# 608_donkey_030200.net
KiCad netlist of a schematic drawn in EAGLE
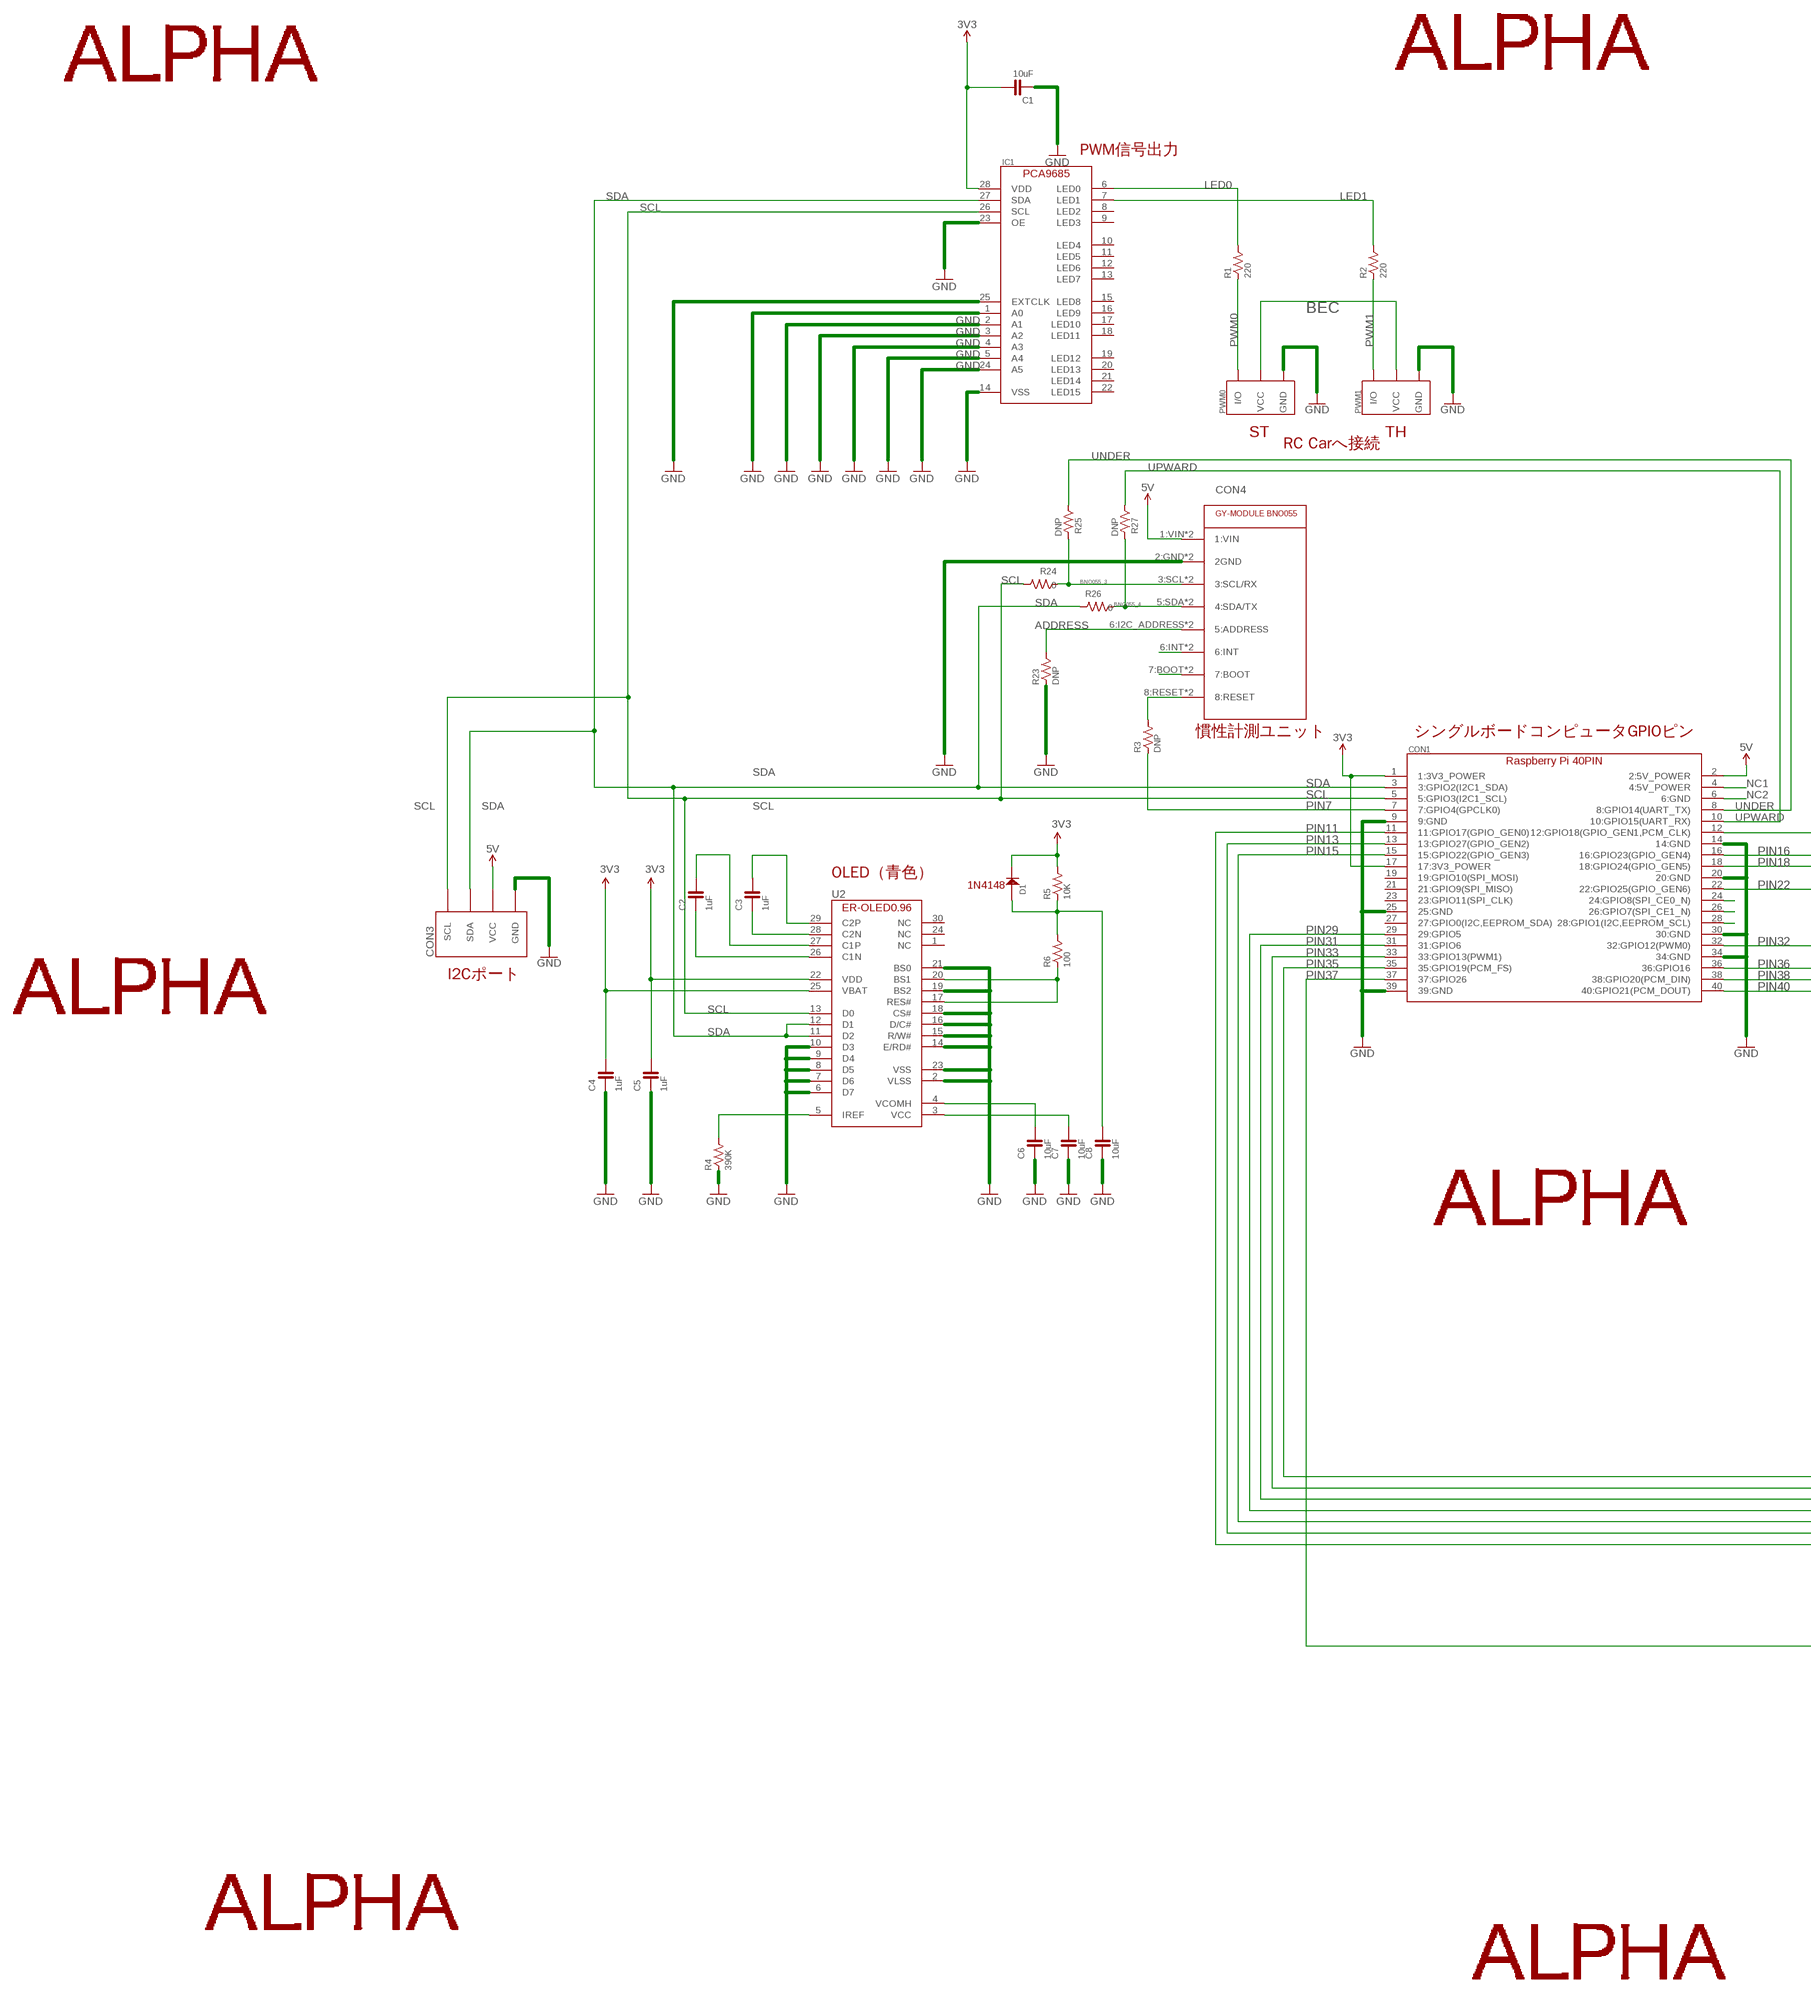
[diagram p0: schematic, sheet 1, part 1 of 3]
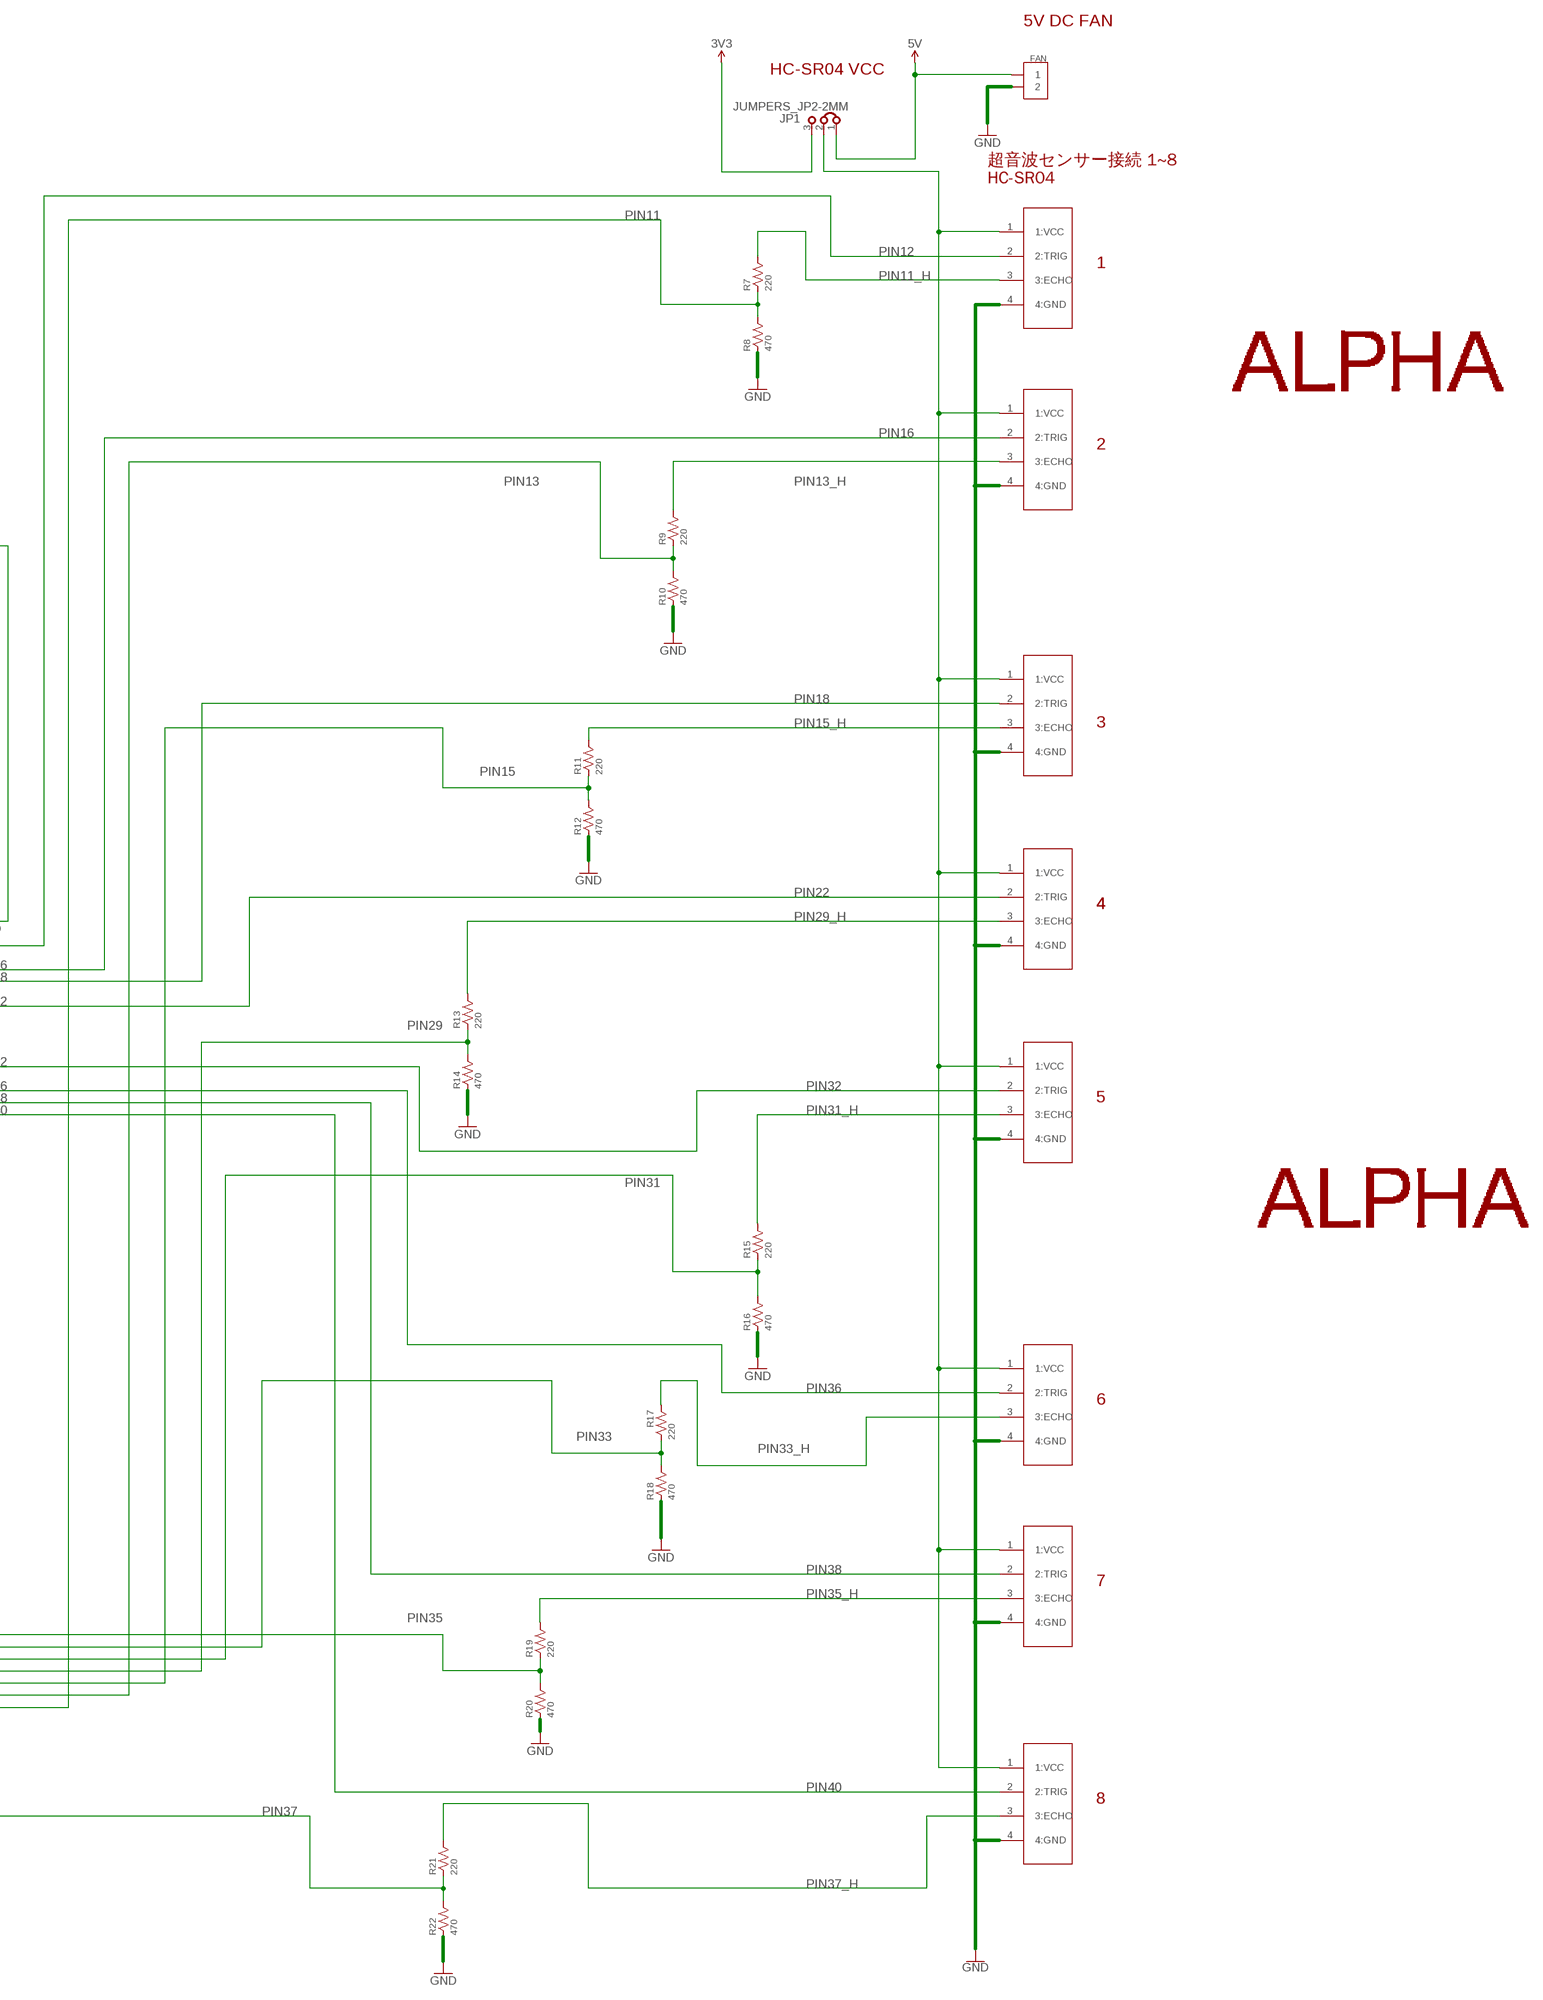
[diagram p1: schematic, sheet 1, part 2 of 3]
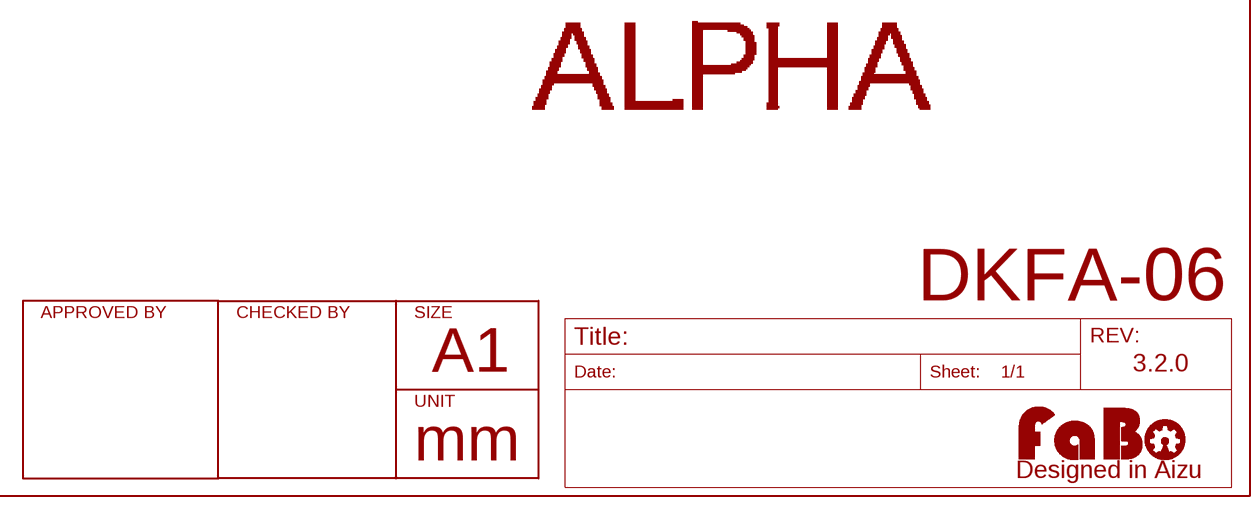
[diagram p2: schematic, sheet 1, part 3 of 3]

(export (version "E")
  (design (tool "Eeschema 10.0.6"))
  (components
    (comp (ref "C1")
      (value "10uF")
      (footprint "eagle-import:0603")
      (libsource (lib "eagle-import") (part "CAPACITOR-0603"))
    )
    (comp (ref "C2")
      (value "1uF")
      (footprint "eagle-import:0603-BOTTOM")
      (libsource (lib "eagle-import") (part "CAPACITOR-0603-BOTTOM"))
    )
    (comp (ref "C3")
      (value "1uF")
      (footprint "eagle-import:0603-BOTTOM")
      (libsource (lib "eagle-import") (part "CAPACITOR-0603-BOTTOM"))
    )
    (comp (ref "C4")
      (value "1uF")
      (footprint "eagle-import:0603-BOTTOM")
      (libsource (lib "eagle-import") (part "CAPACITOR-0603-BOTTOM"))
    )
    (comp (ref "C5")
      (value "1uF")
      (footprint "eagle-import:0603-BOTTOM")
      (libsource (lib "eagle-import") (part "CAPACITOR-0603-BOTTOM"))
    )
    (comp (ref "C6")
      (value "10uF")
      (footprint "eagle-import:0603-BOTTOM")
      (libsource (lib "eagle-import") (part "CAPACITOR-0603-BOTTOM"))
    )
    (comp (ref "C7")
      (value "10uF")
      (footprint "eagle-import:0603-BOTTOM")
      (libsource (lib "eagle-import") (part "CAPACITOR-0603-BOTTOM"))
    )
    (comp (ref "C8")
      (value "10uF")
      (footprint "eagle-import:0603-BOTTOM")
      (libsource (lib "eagle-import") (part "CAPACITOR-0603-BOTTOM"))
    )
    (comp (ref "CON1")
      (value "RASPBERRYPI_SHEILD")
      (footprint "eagle-import:RASPBERRY_PI_SHILED")
      (libsource (lib "eagle-import") (part "RASPBERRYPI_SHEILD"))
    )
    (comp (ref "CON3")
      (value "FABO_BRICK_I2C-S04B-PASK-2")
      (footprint "eagle-import:FABO_BRICK_I2C_S04B-PASK-2")
      (libsource (lib "eagle-import") (part "FABO_BRICK_I2C-S04B-PASK-2"))
    )
    (comp (ref "CON4")
      (value "GY-MODULE_BNO055")
      (footprint "eagle-import:GY-MODULE_BNO055")
      (libsource (lib "eagle-import") (part "GY-MODULE_BNO055"))
    )
    (comp (ref "D1")
      (value "1N4148")
      (footprint "eagle-import:1N4148W")
      (libsource (lib "eagle-import") (part "1N4148"))
    )
    (comp (ref "FAN")
      (value "PIN_1X2")
      (footprint "eagle-import:PIN_1X2")
      (libsource (lib "eagle-import") (part "PIN_1X2"))
    )
    (comp (ref "HC1")
      (value "HC-SR04CONHS-SR04CON-SPEACING")
      (footprint "eagle-import:HC-SR04CON-SPEACE")
      (libsource (lib "eagle-import") (part "HC-SR04CONHS-SR04CON-SPEACING"))
    )
    (comp (ref "HC2")
      (value "HC-SR04CONHS-SR04CON-SPEACING")
      (footprint "eagle-import:HC-SR04CON-SPEACE")
      (libsource (lib "eagle-import") (part "HC-SR04CONHS-SR04CON-SPEACING"))
    )
    (comp (ref "HC3")
      (value "HC-SR04CONHS-SR04CON-SPEACING")
      (footprint "eagle-import:HC-SR04CON-SPEACE")
      (libsource (lib "eagle-import") (part "HC-SR04CONHS-SR04CON-SPEACING"))
    )
    (comp (ref "HC4")
      (value "HC-SR04CONHS-SR04CON-SPEACING")
      (footprint "eagle-import:HC-SR04CON-SPEACE")
      (libsource (lib "eagle-import") (part "HC-SR04CONHS-SR04CON-SPEACING"))
    )
    (comp (ref "HC5")
      (value "HC-SR04CONHS-SR04CON-SPEACING")
      (footprint "eagle-import:HC-SR04CON-SPEACE")
      (libsource (lib "eagle-import") (part "HC-SR04CONHS-SR04CON-SPEACING"))
    )
    (comp (ref "HC6")
      (value "HC-SR04CONHS-SR04CON-SPEACING")
      (footprint "eagle-import:HC-SR04CON-SPEACE")
      (libsource (lib "eagle-import") (part "HC-SR04CONHS-SR04CON-SPEACING"))
    )
    (comp (ref "HC7")
      (value "HC-SR04CONHS-SR04CON-SPEACING")
      (footprint "eagle-import:HC-SR04CON-SPEACE")
      (libsource (lib "eagle-import") (part "HC-SR04CONHS-SR04CON-SPEACING"))
    )
    (comp (ref "HC8")
      (value "HC-SR04CONHS-SR04CON-SPEACING")
      (footprint "eagle-import:HC-SR04CON-SPEACE")
      (libsource (lib "eagle-import") (part "HC-SR04CONHS-SR04CON-SPEACING"))
    )
    (comp (ref "IC1")
      (value "PCA9685BS")
      (footprint "eagle-import:PCA9685")
      (libsource (lib "eagle-import") (part "PCA9685BS"))
    )
    (comp (ref "JP1")
      (value "JUMPERS_JP2-2MM")
      (footprint "eagle-import:JUMPERS_JP2-2MM")
      (libsource (lib "eagle-import") (part "JUMPERS_JP2-2MM"))
    )
    (comp (ref "LOGO1")
      (value "LOGO_FABO-M")
      (footprint "eagle-import:LOGO_FABO_M")
      (libsource (lib "eagle-import") (part "LOGO_FABO-M"))
    )
    (comp (ref "PWM0")
      (value "PWM0")
      (footprint "eagle-import:PIN_1X3_NARROW")
      (libsource (lib "eagle-import") (part "FABO-BRICK-3PIN_HEADER"))
    )
    (comp (ref "PWM1")
      (value "PWM1")
      (footprint "eagle-import:PIN_1X3_NARROW")
      (libsource (lib "eagle-import") (part "FABO-BRICK-3PIN_HEADER"))
    )
    (comp (ref "R1")
      (value "220")
      (footprint "eagle-import:0603")
      (libsource (lib "eagle-import") (part "RESISTOR-0603"))
    )
    (comp (ref "R2")
      (value "220")
      (footprint "eagle-import:0603")
      (libsource (lib "eagle-import") (part "RESISTOR-0603"))
    )
    (comp (ref "R3")
      (value "DNP")
      (footprint "eagle-import:0603-BOTTOM")
      (libsource (lib "eagle-import") (part "RESISTOR-0603-BOTTOM"))
    )
    (comp (ref "R4")
      (value "390K")
      (footprint "eagle-import:0603-BOTTOM")
      (libsource (lib "eagle-import") (part "RESISTOR-0603-BOTTOM"))
    )
    (comp (ref "R5")
      (value "10K")
      (footprint "eagle-import:0603-BOTTOM")
      (libsource (lib "eagle-import") (part "RESISTOR-0603-BOTTOM"))
    )
    (comp (ref "R6")
      (value "100")
      (footprint "eagle-import:0603-BOTTOM")
      (libsource (lib "eagle-import") (part "RESISTOR-0603-BOTTOM"))
    )
    (comp (ref "R7")
      (value "220")
      (footprint "eagle-import:0603")
      (libsource (lib "eagle-import") (part "RESISTOR-0603"))
    )
    (comp (ref "R8")
      (value "470")
      (footprint "eagle-import:0603")
      (libsource (lib "eagle-import") (part "RESISTOR-0603"))
    )
    (comp (ref "R9")
      (value "220")
      (footprint "eagle-import:0603")
      (libsource (lib "eagle-import") (part "RESISTOR-0603"))
    )
    (comp (ref "R10")
      (value "470")
      (footprint "eagle-import:0603")
      (libsource (lib "eagle-import") (part "RESISTOR-0603"))
    )
    (comp (ref "R11")
      (value "220")
      (footprint "eagle-import:0603")
      (libsource (lib "eagle-import") (part "RESISTOR-0603"))
    )
    (comp (ref "R12")
      (value "470")
      (footprint "eagle-import:0603")
      (libsource (lib "eagle-import") (part "RESISTOR-0603"))
    )
    (comp (ref "R13")
      (value "220")
      (footprint "eagle-import:0603")
      (libsource (lib "eagle-import") (part "RESISTOR-0603"))
    )
    (comp (ref "R14")
      (value "470")
      (footprint "eagle-import:0603")
      (libsource (lib "eagle-import") (part "RESISTOR-0603"))
    )
    (comp (ref "R15")
      (value "220")
      (footprint "eagle-import:0603")
      (libsource (lib "eagle-import") (part "RESISTOR-0603"))
    )
    (comp (ref "R16")
      (value "470")
      (footprint "eagle-import:0603")
      (libsource (lib "eagle-import") (part "RESISTOR-0603"))
    )
    (comp (ref "R17")
      (value "220")
      (footprint "eagle-import:0603")
      (libsource (lib "eagle-import") (part "RESISTOR-0603"))
    )
    (comp (ref "R18")
      (value "470")
      (footprint "eagle-import:0603")
      (libsource (lib "eagle-import") (part "RESISTOR-0603"))
    )
    (comp (ref "R19")
      (value "220")
      (footprint "eagle-import:0603")
      (libsource (lib "eagle-import") (part "RESISTOR-0603"))
    )
    (comp (ref "R20")
      (value "470")
      (footprint "eagle-import:0603")
      (libsource (lib "eagle-import") (part "RESISTOR-0603"))
    )
    (comp (ref "R21")
      (value "220")
      (footprint "eagle-import:0603")
      (libsource (lib "eagle-import") (part "RESISTOR-0603"))
    )
    (comp (ref "R22")
      (value "470")
      (footprint "eagle-import:0603")
      (libsource (lib "eagle-import") (part "RESISTOR-0603"))
    )
    (comp (ref "R23")
      (value "DNP")
      (footprint "eagle-import:0603-BOTTOM")
      (libsource (lib "eagle-import") (part "RESISTOR-0603-BOTTOM"))
    )
    (comp (ref "R24")
      (value "0")
      (footprint "eagle-import:0603-BOTTOM")
      (libsource (lib "eagle-import") (part "RESISTOR-0603-BOTTOM"))
    )
    (comp (ref "R25")
      (value "DNP")
      (footprint "eagle-import:0603-BOTTOM")
      (libsource (lib "eagle-import") (part "RESISTOR-0603-BOTTOM"))
    )
    (comp (ref "R26")
      (value "0")
      (footprint "eagle-import:0603-BOTTOM")
      (libsource (lib "eagle-import") (part "RESISTOR-0603-BOTTOM"))
    )
    (comp (ref "R27")
      (value "DNP")
      (footprint "eagle-import:0603-BOTTOM")
      (libsource (lib "eagle-import") (part "RESISTOR-0603-BOTTOM"))
    )
    (comp (ref "U2")
      (value "ER-OLED0.96-1ER-CON30HT-1_REV2")
      (footprint "eagle-import:ER-CON30HT-1_REV2")
      (libsource (lib "eagle-import") (part "ER-OLED0.96-1ER-CON30HT-1_REV2"))
    )
  )
  (nets
    (net (code "1") (name "/ADDRESS") (class "Default")
      (node (ref "CON4") (pin "13:ADDRESSS") (pinfunction "5:ADDRESS_13:ADDRESSS") (pintype "bidirectional"))
      (node (ref "CON4") (pin "6:I2C_ADDRESS") (pinfunction "5:ADDRESS_6:I2C_ADDRESS") (pintype "bidirectional"))
      (node (ref "R23") (pin "2") (pinfunction "2_2") (pintype "bidirectional"))
    )
    (net (code "2") (name "/BEC") (class "Default")
      (node (ref "PWM0") (pin "2") (pinfunction "VCC_2") (pintype "bidirectional"))
      (node (ref "PWM1") (pin "2") (pinfunction "VCC_2") (pintype "bidirectional"))
    )
    (net (code "3") (name "/BNO055_3") (class "Default")
      (node (ref "CON4") (pin "11:SCL") (pinfunction "3:SCL/RX_11:SCL") (pintype "bidirectional"))
      (node (ref "CON4") (pin "3:SCL") (pinfunction "3:SCL/RX_3:SCL") (pintype "bidirectional"))
      (node (ref "R24") (pin "1") (pinfunction "1_1") (pintype "bidirectional"))
      (node (ref "R25") (pin "2") (pinfunction "2_2") (pintype "bidirectional"))
    )
    (net (code "4") (name "/BNO055_4") (class "Default")
      (node (ref "CON4") (pin "12:SDA") (pinfunction "4:SDA/TX_12:SDA") (pintype "bidirectional"))
      (node (ref "CON4") (pin "5:SDA") (pinfunction "4:SDA/TX_5:SDA") (pintype "bidirectional"))
      (node (ref "R26") (pin "1") (pinfunction "1_1") (pintype "bidirectional"))
      (node (ref "R27") (pin "2") (pinfunction "2_2") (pintype "bidirectional"))
    )
    (net (code "5") (name "/LED0") (class "Default")
      (node (ref "IC1") (pin "6") (pinfunction "LED0_6") (pintype "bidirectional"))
      (node (ref "R1") (pin "2") (pinfunction "2_2") (pintype "bidirectional"))
    )
    (net (code "6") (name "/LED1") (class "Default")
      (node (ref "IC1") (pin "7") (pinfunction "LED1_7") (pintype "bidirectional"))
      (node (ref "R2") (pin "2") (pinfunction "2_2") (pintype "bidirectional"))
    )
    (net (code "7") (name "/NC1") (class "Default")
      (node (ref "CON1") (pin "4") (pinfunction "4:5V_POWER_4") (pintype "power_in"))
    )
    (net (code "8") (name "/NC2") (class "Default")
      (node (ref "CON1") (pin "6") (pinfunction "6:GND_6") (pintype "power_in"))
    )
    (net (code "9") (name "/PIN7") (class "Default")
      (node (ref "CON1") (pin "7") (pinfunction "7:GPIO4(GPCLK0)_7") (pintype "bidirectional"))
      (node (ref "R3") (pin "1") (pinfunction "1_1") (pintype "bidirectional"))
    )
    (net (code "10") (name "/PIN11") (class "Default")
      (node (ref "CON1") (pin "11") (pinfunction "11:GPIO17(GPIO_GEN0)_11") (pintype "bidirectional"))
      (node (ref "R7") (pin "1") (pinfunction "1_1") (pintype "bidirectional"))
      (node (ref "R8") (pin "2") (pinfunction "2_2") (pintype "bidirectional"))
    )
    (net (code "11") (name "/PIN11_H") (class "Default")
      (node (ref "HC1") (pin "3") (pinfunction "3:ECHO_3") (pintype "bidirectional"))
      (node (ref "R7") (pin "2") (pinfunction "2_2") (pintype "bidirectional"))
    )
    (net (code "12") (name "/PIN12") (class "Default")
      (node (ref "CON1") (pin "12") (pinfunction "12:GPIO18(GPIO_GEN1,PCM_CLK)_12") (pintype "bidirectional"))
      (node (ref "HC1") (pin "2") (pinfunction "2:TRIG_2") (pintype "bidirectional"))
    )
    (net (code "13") (name "/PIN13") (class "Default")
      (node (ref "CON1") (pin "13") (pinfunction "13:GPIO27(GPIO_GEN2)_13") (pintype "bidirectional"))
      (node (ref "R10") (pin "2") (pinfunction "2_2") (pintype "bidirectional"))
      (node (ref "R9") (pin "1") (pinfunction "1_1") (pintype "bidirectional"))
    )
    (net (code "14") (name "/PIN13_H") (class "Default")
      (node (ref "HC2") (pin "3") (pinfunction "3:ECHO_3") (pintype "bidirectional"))
      (node (ref "R9") (pin "2") (pinfunction "2_2") (pintype "bidirectional"))
    )
    (net (code "15") (name "/PIN15") (class "Default")
      (node (ref "CON1") (pin "15") (pinfunction "15:GPIO22(GPIO_GEN3)_15") (pintype "bidirectional"))
      (node (ref "R11") (pin "1") (pinfunction "1_1") (pintype "bidirectional"))
      (node (ref "R12") (pin "2") (pinfunction "2_2") (pintype "bidirectional"))
    )
    (net (code "16") (name "/PIN15_H") (class "Default")
      (node (ref "HC3") (pin "3") (pinfunction "3:ECHO_3") (pintype "bidirectional"))
      (node (ref "R11") (pin "2") (pinfunction "2_2") (pintype "bidirectional"))
    )
    (net (code "17") (name "/PIN16") (class "Default")
      (node (ref "CON1") (pin "16") (pinfunction "16:GPIO23(GPIO_GEN4)_16") (pintype "bidirectional"))
      (node (ref "HC2") (pin "2") (pinfunction "2:TRIG_2") (pintype "bidirectional"))
    )
    (net (code "18") (name "/PIN18") (class "Default")
      (node (ref "CON1") (pin "18") (pinfunction "18:GPIO24(GPIO_GEN5)_18") (pintype "bidirectional"))
      (node (ref "HC3") (pin "2") (pinfunction "2:TRIG_2") (pintype "bidirectional"))
    )
    (net (code "19") (name "/PIN22") (class "Default")
      (node (ref "CON1") (pin "22") (pinfunction "22:GPIO25(GPIO_GEN6)_22") (pintype "bidirectional"))
      (node (ref "HC4") (pin "2") (pinfunction "2:TRIG_2") (pintype "bidirectional"))
    )
    (net (code "20") (name "/PIN29") (class "Default")
      (node (ref "CON1") (pin "29") (pinfunction "29:GPIO5_29") (pintype "bidirectional"))
      (node (ref "R13") (pin "1") (pinfunction "1_1") (pintype "bidirectional"))
      (node (ref "R14") (pin "2") (pinfunction "2_2") (pintype "bidirectional"))
    )
    (net (code "21") (name "/PIN29_H") (class "Default")
      (node (ref "HC4") (pin "3") (pinfunction "3:ECHO_3") (pintype "bidirectional"))
      (node (ref "R13") (pin "2") (pinfunction "2_2") (pintype "bidirectional"))
    )
    (net (code "22") (name "/PIN31") (class "Default")
      (node (ref "CON1") (pin "31") (pinfunction "31:GPIO6_31") (pintype "bidirectional"))
      (node (ref "R15") (pin "1") (pinfunction "1_1") (pintype "bidirectional"))
      (node (ref "R16") (pin "2") (pinfunction "2_2") (pintype "bidirectional"))
    )
    (net (code "23") (name "/PIN31_H") (class "Default")
      (node (ref "HC5") (pin "3") (pinfunction "3:ECHO_3") (pintype "bidirectional"))
      (node (ref "R15") (pin "2") (pinfunction "2_2") (pintype "bidirectional"))
    )
    (net (code "24") (name "/PIN32") (class "Default")
      (node (ref "CON1") (pin "32") (pinfunction "32:GPIO12(PWM0)_32") (pintype "bidirectional"))
      (node (ref "HC5") (pin "2") (pinfunction "2:TRIG_2") (pintype "bidirectional"))
    )
    (net (code "25") (name "/PIN33") (class "Default")
      (node (ref "CON1") (pin "33") (pinfunction "33:GPIO13(PWM1)_33") (pintype "bidirectional"))
      (node (ref "R17") (pin "1") (pinfunction "1_1") (pintype "bidirectional"))
      (node (ref "R18") (pin "2") (pinfunction "2_2") (pintype "bidirectional"))
    )
    (net (code "26") (name "/PIN33_H") (class "Default")
      (node (ref "HC6") (pin "3") (pinfunction "3:ECHO_3") (pintype "bidirectional"))
      (node (ref "R17") (pin "2") (pinfunction "2_2") (pintype "bidirectional"))
    )
    (net (code "27") (name "/PIN35") (class "Default")
      (node (ref "CON1") (pin "35") (pinfunction "35:GPIO19(PCM_FS)_35") (pintype "bidirectional"))
      (node (ref "R19") (pin "1") (pinfunction "1_1") (pintype "bidirectional"))
      (node (ref "R20") (pin "2") (pinfunction "2_2") (pintype "bidirectional"))
    )
    (net (code "28") (name "/PIN35_H") (class "Default")
      (node (ref "HC7") (pin "3") (pinfunction "3:ECHO_3") (pintype "bidirectional"))
      (node (ref "R19") (pin "2") (pinfunction "2_2") (pintype "bidirectional"))
    )
    (net (code "29") (name "/PIN36") (class "Default")
      (node (ref "CON1") (pin "36") (pinfunction "36:GPIO16_36") (pintype "bidirectional"))
      (node (ref "HC6") (pin "2") (pinfunction "2:TRIG_2") (pintype "bidirectional"))
    )
    (net (code "30") (name "/PIN37") (class "Default")
      (node (ref "CON1") (pin "37") (pinfunction "37:GPIO26_37") (pintype "bidirectional"))
      (node (ref "R21") (pin "1") (pinfunction "1_1") (pintype "bidirectional"))
      (node (ref "R22") (pin "2") (pinfunction "2_2") (pintype "bidirectional"))
    )
    (net (code "31") (name "/PIN37_H") (class "Default")
      (node (ref "HC8") (pin "3") (pinfunction "3:ECHO_3") (pintype "bidirectional"))
      (node (ref "R21") (pin "2") (pinfunction "2_2") (pintype "bidirectional"))
    )
    (net (code "32") (name "/PIN38") (class "Default")
      (node (ref "CON1") (pin "38") (pinfunction "38:GPIO20(PCM_DIN)_38") (pintype "bidirectional"))
      (node (ref "HC7") (pin "2") (pinfunction "2:TRIG_2") (pintype "bidirectional"))
    )
    (net (code "33") (name "/PIN40") (class "Default")
      (node (ref "CON1") (pin "40") (pinfunction "40:GPIO21(PCM_DOUT)_40") (pintype "bidirectional"))
      (node (ref "HC8") (pin "2") (pinfunction "2:TRIG_2") (pintype "bidirectional"))
    )
    (net (code "34") (name "/PWM0") (class "Default")
      (node (ref "PWM0") (pin "1") (pinfunction "I/O_1") (pintype "bidirectional"))
      (node (ref "R1") (pin "1") (pinfunction "1_1") (pintype "bidirectional"))
    )
    (net (code "35") (name "/PWM1") (class "Default")
      (node (ref "PWM1") (pin "1") (pinfunction "I/O_1") (pintype "bidirectional"))
      (node (ref "R2") (pin "1") (pinfunction "1_1") (pintype "bidirectional"))
    )
    (net (code "36") (name "/SCL") (class "Default")
      (node (ref "CON1") (pin "5") (pinfunction "5:GPIO3(I2C1_SCL)_5") (pintype "bidirectional"))
      (node (ref "CON3") (pin "SCL") (pinfunction "SCL_SCL") (pintype "bidirectional"))
      (node (ref "IC1") (pin "26") (pinfunction "SCL_26") (pintype "bidirectional"))
      (node (ref "R24") (pin "2") (pinfunction "2_2") (pintype "bidirectional"))
      (node (ref "U2") (pin "13") (pinfunction "D0_13") (pintype "bidirectional"))
    )
    (net (code "37") (name "/SDA") (class "Default")
      (node (ref "CON1") (pin "3") (pinfunction "3:GPIO2(I2C1_SDA)_3") (pintype "bidirectional"))
      (node (ref "CON3") (pin "SDA") (pinfunction "SDA_SDA") (pintype "bidirectional"))
      (node (ref "IC1") (pin "27") (pinfunction "SDA_27") (pintype "bidirectional"))
      (node (ref "R26") (pin "2") (pinfunction "2_2") (pintype "bidirectional"))
      (node (ref "U2") (pin "11") (pinfunction "D2_11") (pintype "bidirectional"))
      (node (ref "U2") (pin "12") (pinfunction "D1_12") (pintype "bidirectional"))
    )
    (net (code "38") (name "/UNDER") (class "Default")
      (node (ref "CON1") (pin "8") (pinfunction "8:GPIO14(UART_TX)_8") (pintype "bidirectional"))
      (node (ref "R25") (pin "1") (pinfunction "1_1") (pintype "bidirectional"))
    )
    (net (code "39") (name "/UPWARD") (class "Default")
      (node (ref "CON1") (pin "10") (pinfunction "10:GPIO15(UART_RX)_10") (pintype "bidirectional"))
      (node (ref "R27") (pin "1") (pinfunction "1_1") (pintype "bidirectional"))
    )
    (net (code "40") (name "3V3") (class "Default")
      (node (ref "C1") (pin "2") (pinfunction "2_2") (pintype "passive"))
      (node (ref "C4") (pin "2") (pinfunction "2_2") (pintype "passive"))
      (node (ref "C5") (pin "2") (pinfunction "2_2") (pintype "passive"))
      (node (ref "CON1") (pin "1") (pinfunction "1:3V3_POWER_1") (pintype "power_in"))
      (node (ref "CON1") (pin "17") (pinfunction "17:3V3_POWER_17") (pintype "power_in"))
      (node (ref "D1") (pin "CATHODE") (pinfunction "CATHODE_CATHODE") (pintype "bidirectional"))
      (node (ref "IC1") (pin "28") (pinfunction "VDD_28") (pintype "bidirectional"))
      (node (ref "JP1") (pin "3") (pinfunction "3_3") (pintype "passive"))
      (node (ref "R5") (pin "2") (pinfunction "2_2") (pintype "bidirectional"))
      (node (ref "U2") (pin "22") (pinfunction "VDD_22") (pintype "bidirectional"))
      (node (ref "U2") (pin "25") (pinfunction "VBAT_25") (pintype "bidirectional"))
    )
    (net (code "41") (name "5V") (class "Default")
      (node (ref "CON1") (pin "2") (pinfunction "2:5V_POWER_2") (pintype "power_in"))
      (node (ref "CON3") (pin "VCC") (pinfunction "VCC_VCC") (pintype "bidirectional"))
      (node (ref "CON4") (pin "1:VIN") (pinfunction "1:VIN_1:VIN") (pintype "bidirectional"))
      (node (ref "CON4") (pin "9:VIN") (pinfunction "1:VIN_9:VIN") (pintype "bidirectional"))
      (node (ref "FAN") (pin "1") (pinfunction "1_1") (pintype "bidirectional"))
      (node (ref "JP1") (pin "1") (pinfunction "1_1") (pintype "passive"))
    )
    (net (code "42") (name "GND") (class "Default")
      (node (ref "C1") (pin "1") (pinfunction "1_1") (pintype "passive"))
      (node (ref "C4") (pin "1") (pinfunction "1_1") (pintype "passive"))
      (node (ref "C5") (pin "1") (pinfunction "1_1") (pintype "passive"))
      (node (ref "C6") (pin "1") (pinfunction "1_1") (pintype "passive"))
      (node (ref "C7") (pin "1") (pinfunction "1_1") (pintype "passive"))
      (node (ref "C8") (pin "1") (pinfunction "1_1") (pintype "passive"))
      (node (ref "CON1") (pin "14") (pinfunction "14:GND_14") (pintype "power_in"))
      (node (ref "CON1") (pin "20") (pinfunction "20:GND_20") (pintype "power_in"))
      (node (ref "CON1") (pin "25") (pinfunction "25:GND_25") (pintype "power_in"))
      (node (ref "CON1") (pin "30") (pinfunction "30:GND_30") (pintype "power_in"))
      (node (ref "CON1") (pin "34") (pinfunction "34:GND_34") (pintype "power_in"))
      (node (ref "CON1") (pin "39") (pinfunction "39:GND_39") (pintype "power_in"))
      (node (ref "CON1") (pin "9") (pinfunction "9:GND_9") (pintype "power_in"))
      (node (ref "CON3") (pin "GND") (pinfunction "GND_GND") (pintype "bidirectional"))
      (node (ref "CON4") (pin "10:GND") (pinfunction "2GND_10:GND") (pintype "bidirectional"))
      (node (ref "CON4") (pin "2:GND") (pinfunction "2GND_2:GND") (pintype "bidirectional"))
      (node (ref "FAN") (pin "2") (pinfunction "2_2") (pintype "bidirectional"))
      (node (ref "HC1") (pin "4") (pinfunction "4:GND_4") (pintype "bidirectional"))
      (node (ref "HC2") (pin "4") (pinfunction "4:GND_4") (pintype "bidirectional"))
      (node (ref "HC3") (pin "4") (pinfunction "4:GND_4") (pintype "bidirectional"))
      (node (ref "HC4") (pin "4") (pinfunction "4:GND_4") (pintype "bidirectional"))
      (node (ref "HC5") (pin "4") (pinfunction "4:GND_4") (pintype "bidirectional"))
      (node (ref "HC6") (pin "4") (pinfunction "4:GND_4") (pintype "bidirectional"))
      (node (ref "HC7") (pin "4") (pinfunction "4:GND_4") (pintype "bidirectional"))
      (node (ref "HC8") (pin "4") (pinfunction "4:GND_4") (pintype "bidirectional"))
      (node (ref "IC1") (pin "1") (pinfunction "A0_1") (pintype "bidirectional"))
      (node (ref "IC1") (pin "14") (pinfunction "VSS_14") (pintype "bidirectional"))
      (node (ref "IC1") (pin "2") (pinfunction "A1_2") (pintype "bidirectional"))
      (node (ref "IC1") (pin "23") (pinfunction "OE_23") (pintype "bidirectional"))
      (node (ref "IC1") (pin "24") (pinfunction "A5_24") (pintype "bidirectional"))
      (node (ref "IC1") (pin "25") (pinfunction "EXTCLK_25") (pintype "bidirectional"))
      (node (ref "IC1") (pin "3") (pinfunction "A2_3") (pintype "bidirectional"))
      (node (ref "IC1") (pin "4") (pinfunction "A3_4") (pintype "bidirectional"))
      (node (ref "IC1") (pin "5") (pinfunction "A4_5") (pintype "bidirectional"))
      (node (ref "PWM0") (pin "3") (pinfunction "GND_3") (pintype "bidirectional"))
      (node (ref "PWM1") (pin "3") (pinfunction "GND_3") (pintype "bidirectional"))
      (node (ref "R10") (pin "1") (pinfunction "1_1") (pintype "bidirectional"))
      (node (ref "R12") (pin "1") (pinfunction "1_1") (pintype "bidirectional"))
      (node (ref "R14") (pin "1") (pinfunction "1_1") (pintype "bidirectional"))
      (node (ref "R16") (pin "1") (pinfunction "1_1") (pintype "bidirectional"))
      (node (ref "R18") (pin "1") (pinfunction "1_1") (pintype "bidirectional"))
      (node (ref "R20") (pin "1") (pinfunction "1_1") (pintype "bidirectional"))
      (node (ref "R22") (pin "1") (pinfunction "1_1") (pintype "bidirectional"))
      (node (ref "R23") (pin "1") (pinfunction "1_1") (pintype "bidirectional"))
      (node (ref "R4") (pin "1") (pinfunction "1_1") (pintype "bidirectional"))
      (node (ref "R8") (pin "1") (pinfunction "1_1") (pintype "bidirectional"))
      (node (ref "U2") (pin "10") (pinfunction "D3_10") (pintype "bidirectional"))
      (node (ref "U2") (pin "14") (pinfunction "E/RD#_14") (pintype "bidirectional"))
      (node (ref "U2") (pin "15") (pinfunction "R/W#_15") (pintype "bidirectional"))
      (node (ref "U2") (pin "16") (pinfunction "D/C#_16") (pintype "bidirectional"))
      (node (ref "U2") (pin "18") (pinfunction "CS#_18") (pintype "bidirectional"))
      (node (ref "U2") (pin "19") (pinfunction "BS2_19") (pintype "bidirectional"))
      (node (ref "U2") (pin "2") (pinfunction "VLSS_2") (pintype "bidirectional"))
      (node (ref "U2") (pin "21") (pinfunction "BS0_21") (pintype "bidirectional"))
      (node (ref "U2") (pin "23") (pinfunction "VSS_23") (pintype "bidirectional"))
      (node (ref "U2") (pin "6") (pinfunction "D7_6") (pintype "bidirectional"))
      (node (ref "U2") (pin "7") (pinfunction "D6_7") (pintype "bidirectional"))
      (node (ref "U2") (pin "8") (pinfunction "D5_8") (pintype "bidirectional"))
      (node (ref "U2") (pin "9") (pinfunction "D4_9") (pintype "bidirectional"))
    )
    (net (code "43") (name "Net-(C8-Pad2)") (class "Default")
      (node (ref "C8") (pin "2") (pinfunction "2_2") (pintype "passive"))
      (node (ref "D1") (pin "ANODE") (pinfunction "ANODE_ANODE") (pintype "bidirectional"))
      (node (ref "R5") (pin "1") (pinfunction "1_1") (pintype "bidirectional"))
      (node (ref "R6") (pin "2") (pinfunction "2_2") (pintype "bidirectional"))
    )
    (net (code "44") (name "Net-(CON4-6:INT-Pad14:INT)") (class "Default")
      (node (ref "CON4") (pin "14:INT") (pinfunction "6:INT_14:INT") (pintype "bidirectional"))
      (node (ref "CON4") (pin "6:INT") (pinfunction "6:INT_6:INT") (pintype "bidirectional"))
    )
    (net (code "45") (name "Net-(CON4-7:BOOT-Pad15:BOOT)") (class "Default")
      (node (ref "CON4") (pin "15:BOOT") (pinfunction "7:BOOT_15:BOOT") (pintype "bidirectional"))
      (node (ref "CON4") (pin "7:BOOT") (pinfunction "7:BOOT_7:BOOT") (pintype "bidirectional"))
    )
    (net (code "46") (name "Net-(CON4-8:RESET-Pad16:RESET)") (class "Default")
      (node (ref "CON4") (pin "16:RESET") (pinfunction "8:RESET_16:RESET") (pintype "bidirectional"))
      (node (ref "CON4") (pin "8:RESET") (pinfunction "8:RESET_8:RESET") (pintype "bidirectional"))
      (node (ref "R3") (pin "2") (pinfunction "2_2") (pintype "bidirectional"))
    )
    (net (code "47") (name "Net-(HC1-1:VCC)") (class "Default")
      (node (ref "HC1") (pin "1") (pinfunction "1:VCC_1") (pintype "bidirectional"))
      (node (ref "HC2") (pin "1") (pinfunction "1:VCC_1") (pintype "bidirectional"))
      (node (ref "HC3") (pin "1") (pinfunction "1:VCC_1") (pintype "bidirectional"))
      (node (ref "HC4") (pin "1") (pinfunction "1:VCC_1") (pintype "bidirectional"))
      (node (ref "HC5") (pin "1") (pinfunction "1:VCC_1") (pintype "bidirectional"))
      (node (ref "HC6") (pin "1") (pinfunction "1:VCC_1") (pintype "bidirectional"))
      (node (ref "HC7") (pin "1") (pinfunction "1:VCC_1") (pintype "bidirectional"))
      (node (ref "HC8") (pin "1") (pinfunction "1:VCC_1") (pintype "bidirectional"))
      (node (ref "JP1") (pin "2") (pinfunction "2_2") (pintype "passive"))
    )
    (net (code "48") (name "Net-(U2-BS1)") (class "Default")
      (node (ref "R6") (pin "1") (pinfunction "1_1") (pintype "bidirectional"))
      (node (ref "U2") (pin "17") (pinfunction "RES#_17") (pintype "bidirectional"))
      (node (ref "U2") (pin "20") (pinfunction "BS1_20") (pintype "bidirectional"))
    )
    (net (code "49") (name "Net-(U2-C1N)") (class "Default")
      (node (ref "C2") (pin "1") (pinfunction "1_1") (pintype "passive"))
      (node (ref "U2") (pin "26") (pinfunction "C1N_26") (pintype "bidirectional"))
    )
    (net (code "50") (name "Net-(U2-C1P)") (class "Default")
      (node (ref "C2") (pin "2") (pinfunction "2_2") (pintype "passive"))
      (node (ref "U2") (pin "27") (pinfunction "C1P_27") (pintype "bidirectional"))
    )
    (net (code "51") (name "Net-(U2-C2N)") (class "Default")
      (node (ref "C3") (pin "1") (pinfunction "1_1") (pintype "passive"))
      (node (ref "U2") (pin "28") (pinfunction "C2N_28") (pintype "bidirectional"))
    )
    (net (code "52") (name "Net-(U2-C2P)") (class "Default")
      (node (ref "C3") (pin "2") (pinfunction "2_2") (pintype "passive"))
      (node (ref "U2") (pin "29") (pinfunction "C2P_29") (pintype "bidirectional"))
    )
    (net (code "53") (name "Net-(U2-IREF)") (class "Default")
      (node (ref "R4") (pin "2") (pinfunction "2_2") (pintype "bidirectional"))
      (node (ref "U2") (pin "5") (pinfunction "IREF_5") (pintype "bidirectional"))
    )
    (net (code "54") (name "Net-(U2-VCC)") (class "Default")
      (node (ref "C7") (pin "2") (pinfunction "2_2") (pintype "passive"))
      (node (ref "U2") (pin "3") (pinfunction "VCC_3") (pintype "bidirectional"))
    )
    (net (code "55") (name "Net-(U2-VCOMH)") (class "Default")
      (node (ref "C6") (pin "2") (pinfunction "2_2") (pintype "passive"))
      (node (ref "U2") (pin "4") (pinfunction "VCOMH_4") (pintype "bidirectional"))
    )
    (net (code "56") (name "unconnected-(CON1-19:GPIO10(SPI_MOSI)-Pad19)") (class "Default")
      (node (ref "CON1") (pin "19") (pinfunction "19:GPIO10(SPI_MOSI)_19") (pintype "bidirectional"))
    )
    (net (code "57") (name "unconnected-(CON1-21:GPIO9(SPI_MISO)-Pad21)") (class "Default")
      (node (ref "CON1") (pin "21") (pinfunction "21:GPIO9(SPI_MISO)_21") (pintype "bidirectional"))
    )
    (net (code "58") (name "unconnected-(CON1-23:GPIO11(SPI_CLK)-Pad23)") (class "Default")
      (node (ref "CON1") (pin "23") (pinfunction "23:GPIO11(SPI_CLK)_23") (pintype "bidirectional"))
    )
    (net (code "59") (name "unconnected-(CON1-24:GPIO8(SPI_CE0_N)-Pad24)") (class "Default")
      (node (ref "CON1") (pin "24") (pinfunction "24:GPIO8(SPI_CE0_N)_24") (pintype "bidirectional"))
    )
    (net (code "60") (name "unconnected-(CON1-26:GPIO7(SPI_CE1_N)-Pad26)") (class "Default")
      (node (ref "CON1") (pin "26") (pinfunction "26:GPIO7(SPI_CE1_N)_26") (pintype "bidirectional"))
    )
    (net (code "61") (name "unconnected-(CON1-27:GPIO0(I2C,EEPROM_SDA)-Pad27)") (class "Default")
      (node (ref "CON1") (pin "27") (pinfunction "27:GPIO0(I2C,EEPROM_SDA)_27") (pintype "bidirectional"))
    )
    (net (code "62") (name "unconnected-(CON1-28:GPIO1(I2C,EEPROM_SCL)-Pad28)") (class "Default")
      (node (ref "CON1") (pin "28") (pinfunction "28:GPIO1(I2C,EEPROM_SCL)_28") (pintype "bidirectional"))
    )
    (net (code "63") (name "unconnected-(IC1-LED2-Pad8)") (class "Default")
      (node (ref "IC1") (pin "8") (pinfunction "LED2_8") (pintype "bidirectional"))
    )
    (net (code "64") (name "unconnected-(IC1-LED3-Pad9)") (class "Default")
      (node (ref "IC1") (pin "9") (pinfunction "LED3_9") (pintype "bidirectional"))
    )
    (net (code "65") (name "unconnected-(IC1-LED4-Pad10)") (class "Default")
      (node (ref "IC1") (pin "10") (pinfunction "LED4_10") (pintype "bidirectional"))
    )
    (net (code "66") (name "unconnected-(IC1-LED5-Pad11)") (class "Default")
      (node (ref "IC1") (pin "11") (pinfunction "LED5_11") (pintype "bidirectional"))
    )
    (net (code "67") (name "unconnected-(IC1-LED6-Pad12)") (class "Default")
      (node (ref "IC1") (pin "12") (pinfunction "LED6_12") (pintype "bidirectional"))
    )
    (net (code "68") (name "unconnected-(IC1-LED7-Pad13)") (class "Default")
      (node (ref "IC1") (pin "13") (pinfunction "LED7_13") (pintype "bidirectional"))
    )
    (net (code "69") (name "unconnected-(IC1-LED8-Pad15)") (class "Default")
      (node (ref "IC1") (pin "15") (pinfunction "LED8_15") (pintype "bidirectional"))
    )
    (net (code "70") (name "unconnected-(IC1-LED9-Pad16)") (class "Default")
      (node (ref "IC1") (pin "16") (pinfunction "LED9_16") (pintype "bidirectional"))
    )
    (net (code "71") (name "unconnected-(IC1-LED10-Pad17)") (class "Default")
      (node (ref "IC1") (pin "17") (pinfunction "LED10_17") (pintype "bidirectional"))
    )
    (net (code "72") (name "unconnected-(IC1-LED11-Pad18)") (class "Default")
      (node (ref "IC1") (pin "18") (pinfunction "LED11_18") (pintype "bidirectional"))
    )
    (net (code "73") (name "unconnected-(IC1-LED12-Pad19)") (class "Default")
      (node (ref "IC1") (pin "19") (pinfunction "LED12_19") (pintype "bidirectional"))
    )
    (net (code "74") (name "unconnected-(IC1-LED13-Pad20)") (class "Default")
      (node (ref "IC1") (pin "20") (pinfunction "LED13_20") (pintype "bidirectional"))
    )
    (net (code "75") (name "unconnected-(IC1-LED14-Pad21)") (class "Default")
      (node (ref "IC1") (pin "21") (pinfunction "LED14_21") (pintype "bidirectional"))
    )
    (net (code "76") (name "unconnected-(IC1-LED15-Pad22)") (class "Default")
      (node (ref "IC1") (pin "22") (pinfunction "LED15_22") (pintype "bidirectional"))
    )
    (net (code "77") (name "unconnected-(U2-NC-Pad1)") (class "Default")
      (node (ref "U2") (pin "1") (pinfunction "NC_1") (pintype "bidirectional"))
    )
    (net (code "78") (name "unconnected-(U2-NC-Pad24)") (class "Default")
      (node (ref "U2") (pin "24") (pinfunction "NC_24") (pintype "bidirectional"))
    )
    (net (code "79") (name "unconnected-(U2-NC-Pad30)") (class "Default")
      (node (ref "U2") (pin "30") (pinfunction "NC_30") (pintype "bidirectional"))
    )
  )
)
